# H0ARAx_Frontend.net
KiCad netlist of a schematic drawn in Altium Designer
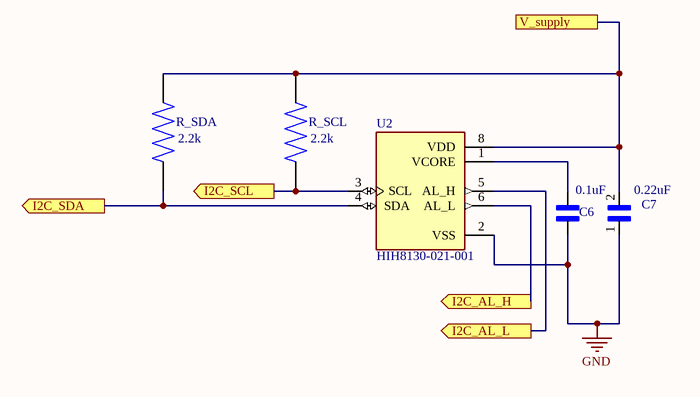
[diagram p0: H0ARAx_Frontend.SchDoc]

(export (version "E")
  (design (tool "Eeschema 10.0.6"))
  (components
    (comp (ref "C6")
      (value "0.1uF")
      (footprint "CAPC0603X33N")
      (description "0.1 ÂµF Â±10% 16V Ceramic Capacitor X7S 0201 (0603 Metric)")
      (fields (field (name "MF") "Murata Electronics") (field (name "MP") "GRM033C71C104KE14D"))
      (libsource (lib "GRM033C71C104KE14D") (part "GRM033C71C104KE14D"))
    )
    (comp (ref "C7")
      (value "0.22uF")
      (footprint "CAPC0603X33N")
      (description "SMD Capacitor X7R_EIA_ with Capacitance: 0.22uF Tol. 10%. Rated Voltage: 16Vdc")
      (fields (field (name "MP") "GRM188R71C224KA01D") (field (name "MF") "Murata"))
      (libsource (lib "SnapEDAsch") (part "GRM188R71C224KA01D"))
    )
    (comp (ref "R_SCL")
      (value "2.2k")
      (footprint "RESC1608X55N")
      (description "Fixed Resistor CRGCQ 0603 2K2 5%")
      (fields (field (name "MF") "TE Connectivity") (field (name "MP") "CRGCQ0603J2K2"))
      (libsource (lib "CRGCQ0603J2K2") (part "CRGCQ0603J2K2"))
    )
    (comp (ref "R_SDA")
      (value "2.2k")
      (footprint "RESC1608X55N")
      (description "Fixed Resistor CRGCQ 0603 2K2 5%")
      (fields (field (name "MF") "TE Connectivity") (field (name "MP") "CRGCQ0603J2K2"))
      (libsource (lib "CRGCQ0603J2K2") (part "CRGCQ0603J2K2"))
    )
    (comp (ref "U2")
      (value "HIH8130-021-001")
      (footprint "SOIC127P600X206-8N")
      (fields (field (name "MF") "{'manufacturer': u'Honeywell Sensing and Productivity Solutions'}"))
      (libsource (lib "HIH8130-021-001") (part "HIH8130-021-001"))
    )
  )
  (nets
    (net (code "1") (name "/I2C_AL_H") (class "Default")
      (node (ref "U2") (pin "6") (pinfunction "AL_L_6") (pintype "output"))
    )
    (net (code "2") (name "/I2C_AL_L") (class "Default")
      (node (ref "U2") (pin "5") (pinfunction "AL_H_5") (pintype "output"))
    )
    (net (code "3") (name "/I2C_SCL") (class "Default")
      (node (ref "R_SCL") (pin "1") (pinfunction "1_1") (pintype "passive"))
      (node (ref "U2") (pin "3") (pinfunction "SCL_3") (pintype "bidirectional"))
    )
    (net (code "4") (name "/I2C_SDA") (class "Default")
      (node (ref "R_SDA") (pin "1") (pinfunction "1_1") (pintype "passive"))
      (node (ref "U2") (pin "4") (pinfunction "SDA_4") (pintype "bidirectional"))
    )
    (net (code "5") (name "/V_supply") (class "Default")
      (node (ref "C7") (pin "2") (pinfunction "2_2") (pintype "passive"))
      (node (ref "R_SCL") (pin "2") (pinfunction "2_2") (pintype "passive"))
      (node (ref "R_SDA") (pin "2") (pinfunction "2_2") (pintype "passive"))
      (node (ref "U2") (pin "8") (pinfunction "VDD_8") (pintype "power_in"))
    )
    (net (code "6") (name "GND") (class "Default")
      (node (ref "C6") (pin "1") (pinfunction "1_1") (pintype "passive"))
      (node (ref "C7") (pin "1") (pinfunction "1_1") (pintype "passive"))
      (node (ref "U2") (pin "2") (pinfunction "VSS_2") (pintype "power_in"))
    )
    (net (code "7") (name "Net-(U2-VCORE)") (class "Default")
      (node (ref "C6") (pin "2") (pinfunction "2_2") (pintype "passive"))
      (node (ref "U2") (pin "1") (pinfunction "VCORE_1") (pintype "power_in"))
    )
  )
)
